# ATmegaExtOscillator.net
KiCad netlist of a schematic drawn in EAGLE
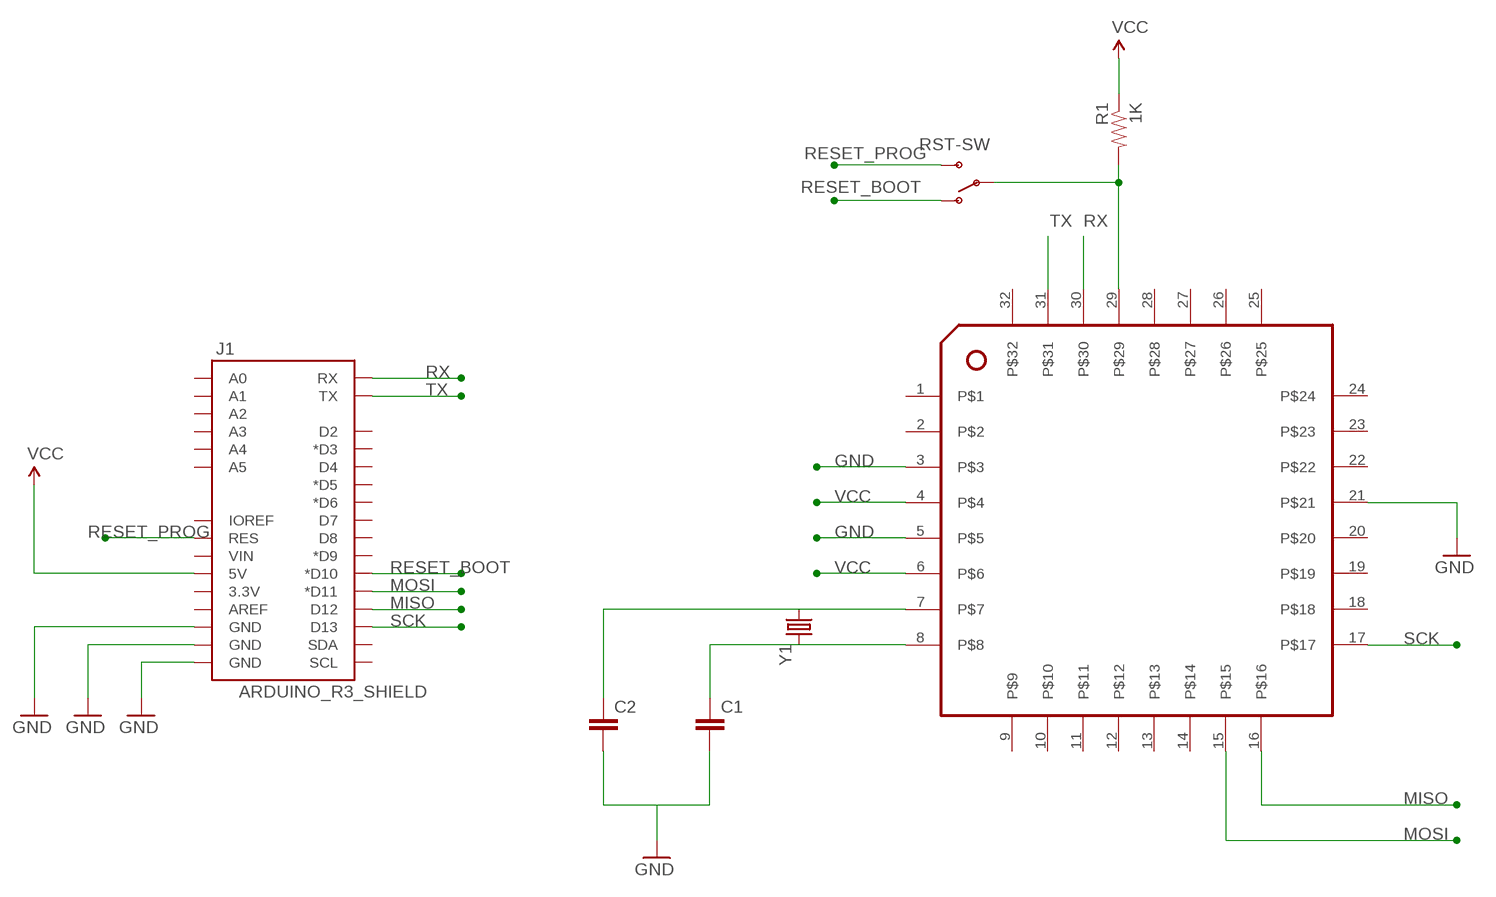
[diagram p0: schematic, sheet 1]

(export (version "E")
  (design (tool "Eeschema 10.0.6"))
  (components
    (comp (ref "C1")
      (value "0.1UF-50V-20%(PTH)KIT-EZ")
      (footprint "eagle-import:CAP-PTH-SMALL-KIT")
      (libsource (lib "eagle-import") (part "0.1UF-50V-20%(PTH)KIT-EZ"))
    )
    (comp (ref "C2")
      (value "0.1UF-50V-20%(PTH)KIT-EZ")
      (footprint "eagle-import:CAP-PTH-SMALL-KIT")
      (libsource (lib "eagle-import") (part "0.1UF-50V-20%(PTH)KIT-EZ"))
    )
    (comp (ref "J1")
      (value "ARDUINO_R3_SHIELD")
      (footprint "eagle-import:UNO_R3_SHIELD")
      (libsource (lib "eagle-import") (part "ARDUINO_R3_SHIELD"))
    )
    (comp (ref "R1")
      (value "1K")
      (footprint "eagle-import:AXIAL-0.3")
      (libsource (lib "eagle-import") (part "1KOHM-1/4W-1%(PTH)"))
    )
    (comp (ref "RST-SW")
      (value "SWITCH-SPDTPTH")
      (footprint "eagle-import:SWITCH-SPDT")
      (libsource (lib "eagle-import") (part "SWITCH-SPDTPTH"))
    )
    (comp (ref "U$1")
      (value "ATMEGA-TQFP-BREAKOUT")
      (footprint "eagle-import:TQFP32-BREAKOUT")
      (libsource (lib "eagle-import") (part "ATMEGA-TQFP-BREAKOUT"))
    )
    (comp (ref "Y1")
      (value "CRYSTALHC49US")
      (footprint "eagle-import:HC49US")
      (libsource (lib "eagle-import") (part "CRYSTALHC49US"))
    )
  )
  (nets
    (net (code "1") (name "/MISO") (class "Default")
      (node (ref "J1") (pin "D12") (pinfunction "D12_D12") (pintype "bidirectional"))
      (node (ref "U$1") (pin "16") (pinfunction "P$16_16") (pintype "bidirectional"))
    )
    (net (code "2") (name "/MOSI") (class "Default")
      (node (ref "J1") (pin "D11") (pinfunction "*D11_D11") (pintype "bidirectional"))
      (node (ref "U$1") (pin "15") (pinfunction "P$15_15") (pintype "bidirectional"))
    )
    (net (code "3") (name "/RESET_BOOT") (class "Default")
      (node (ref "J1") (pin "D10") (pinfunction "*D10_D10") (pintype "bidirectional"))
      (node (ref "RST-SW") (pin "1") (pinfunction "O_1") (pintype "passive"))
    )
    (net (code "4") (name "/RESET_PROG") (class "Default")
      (node (ref "J1") (pin "RES") (pinfunction "RES_RES") (pintype "bidirectional"))
      (node (ref "RST-SW") (pin "3") (pinfunction "S_3") (pintype "passive"))
    )
    (net (code "5") (name "/RX") (class "Default")
      (node (ref "J1") (pin "RX") (pinfunction "RX_RX") (pintype "bidirectional"))
      (node (ref "U$1") (pin "30") (pinfunction "P$30_30") (pintype "bidirectional"))
    )
    (net (code "6") (name "/SCK") (class "Default")
      (node (ref "J1") (pin "D13") (pinfunction "D13_D13") (pintype "bidirectional"))
      (node (ref "U$1") (pin "17") (pinfunction "P$17_17") (pintype "bidirectional"))
    )
    (net (code "7") (name "/TX") (class "Default")
      (node (ref "J1") (pin "TX") (pinfunction "TX_TX") (pintype "bidirectional"))
      (node (ref "U$1") (pin "31") (pinfunction "P$31_31") (pintype "bidirectional"))
    )
    (net (code "8") (name "GND") (class "Default")
      (node (ref "C1") (pin "2") (pinfunction "2_2") (pintype "passive"))
      (node (ref "C2") (pin "2") (pinfunction "2_2") (pintype "passive"))
      (node (ref "J1") (pin "GND@0") (pinfunction "GND_GND@0") (pintype "bidirectional"))
      (node (ref "J1") (pin "GND@1") (pinfunction "GND_GND@1") (pintype "bidirectional"))
      (node (ref "J1") (pin "GND@2") (pinfunction "GND_GND@2") (pintype "bidirectional"))
      (node (ref "U$1") (pin "21") (pinfunction "P$21_21") (pintype "bidirectional"))
      (node (ref "U$1") (pin "3") (pinfunction "P$3_3") (pintype "bidirectional"))
      (node (ref "U$1") (pin "5") (pinfunction "P$5_5") (pintype "bidirectional"))
    )
    (net (code "9") (name "Net-(R1-2)") (class "Default")
      (node (ref "R1") (pin "P$2") (pinfunction "2_P$2") (pintype "passive"))
      (node (ref "RST-SW") (pin "2") (pinfunction "P_2") (pintype "passive"))
      (node (ref "U$1") (pin "29") (pinfunction "P$29_29") (pintype "bidirectional"))
    )
    (net (code "10") (name "Net-(U$1-P$7)") (class "Default")
      (node (ref "C2") (pin "1") (pinfunction "1_1") (pintype "passive"))
      (node (ref "U$1") (pin "7") (pinfunction "P$7_7") (pintype "bidirectional"))
      (node (ref "Y1") (pin "1") (pinfunction "1_1") (pintype "passive"))
    )
    (net (code "11") (name "Net-(U$1-P$8)") (class "Default")
      (node (ref "C1") (pin "1") (pinfunction "1_1") (pintype "passive"))
      (node (ref "U$1") (pin "8") (pinfunction "P$8_8") (pintype "bidirectional"))
      (node (ref "Y1") (pin "2") (pinfunction "2_2") (pintype "passive"))
    )
    (net (code "12") (name "VCC") (class "Default")
      (node (ref "J1") (pin "5V") (pinfunction "5V_5V") (pintype "bidirectional"))
      (node (ref "R1") (pin "P$1") (pinfunction "1_P$1") (pintype "passive"))
      (node (ref "U$1") (pin "4") (pinfunction "P$4_4") (pintype "bidirectional"))
      (node (ref "U$1") (pin "6") (pinfunction "P$6_6") (pintype "bidirectional"))
    )
    (net (code "13") (name "unconnected-(J1-*D3-PadD3)") (class "Default")
      (node (ref "J1") (pin "D3") (pinfunction "*D3_D3") (pintype "bidirectional"))
    )
    (net (code "14") (name "unconnected-(J1-*D5-PadD5)") (class "Default")
      (node (ref "J1") (pin "D5") (pinfunction "*D5_D5") (pintype "bidirectional"))
    )
    (net (code "15") (name "unconnected-(J1-*D6-PadD6)") (class "Default")
      (node (ref "J1") (pin "D6") (pinfunction "*D6_D6") (pintype "bidirectional"))
    )
    (net (code "16") (name "unconnected-(J1-*D9-PadD9)") (class "Default")
      (node (ref "J1") (pin "D9") (pinfunction "*D9_D9") (pintype "bidirectional"))
    )
    (net (code "17") (name "unconnected-(J1-Pad3.3V)") (class "Default")
      (node (ref "J1") (pin "3.3V") (pinfunction "3.3V_3.3V") (pintype "bidirectional"))
    )
    (net (code "18") (name "unconnected-(J1-PadA0)") (class "Default")
      (node (ref "J1") (pin "A0") (pinfunction "A0_A0") (pintype "bidirectional"))
    )
    (net (code "19") (name "unconnected-(J1-PadA1)") (class "Default")
      (node (ref "J1") (pin "A1") (pinfunction "A1_A1") (pintype "bidirectional"))
    )
    (net (code "20") (name "unconnected-(J1-PadA2)") (class "Default")
      (node (ref "J1") (pin "A2") (pinfunction "A2_A2") (pintype "bidirectional"))
    )
    (net (code "21") (name "unconnected-(J1-PadA3)") (class "Default")
      (node (ref "J1") (pin "A3") (pinfunction "A3_A3") (pintype "bidirectional"))
    )
    (net (code "22") (name "unconnected-(J1-PadA4)") (class "Default")
      (node (ref "J1") (pin "A4") (pinfunction "A4_A4") (pintype "bidirectional"))
    )
    (net (code "23") (name "unconnected-(J1-PadA5)") (class "Default")
      (node (ref "J1") (pin "A5") (pinfunction "A5_A5") (pintype "bidirectional"))
    )
    (net (code "24") (name "unconnected-(J1-PadAREF)") (class "Default")
      (node (ref "J1") (pin "AREF") (pinfunction "AREF_AREF") (pintype "bidirectional"))
    )
    (net (code "25") (name "unconnected-(J1-PadD2)") (class "Default")
      (node (ref "J1") (pin "D2") (pinfunction "D2_D2") (pintype "bidirectional"))
    )
    (net (code "26") (name "unconnected-(J1-PadD4)") (class "Default")
      (node (ref "J1") (pin "D4") (pinfunction "D4_D4") (pintype "bidirectional"))
    )
    (net (code "27") (name "unconnected-(J1-PadD7)") (class "Default")
      (node (ref "J1") (pin "D7") (pinfunction "D7_D7") (pintype "bidirectional"))
    )
    (net (code "28") (name "unconnected-(J1-PadD8)") (class "Default")
      (node (ref "J1") (pin "D8") (pinfunction "D8_D8") (pintype "bidirectional"))
    )
    (net (code "29") (name "unconnected-(J1-PadIOREF)") (class "Default")
      (node (ref "J1") (pin "IOREF") (pinfunction "IOREF_IOREF") (pintype "bidirectional"))
    )
    (net (code "30") (name "unconnected-(J1-PadSCL)") (class "Default")
      (node (ref "J1") (pin "SCL") (pinfunction "SCL_SCL") (pintype "bidirectional"))
    )
    (net (code "31") (name "unconnected-(J1-PadSDA)") (class "Default")
      (node (ref "J1") (pin "SDA") (pinfunction "SDA_SDA") (pintype "bidirectional"))
    )
    (net (code "32") (name "unconnected-(J1-PadVIN)") (class "Default")
      (node (ref "J1") (pin "VIN") (pinfunction "VIN_VIN") (pintype "bidirectional"))
    )
    (net (code "33") (name "unconnected-(U$1-P$1-Pad1)") (class "Default")
      (node (ref "U$1") (pin "1") (pinfunction "P$1_1") (pintype "bidirectional"))
    )
    (net (code "34") (name "unconnected-(U$1-P$2-Pad2)") (class "Default")
      (node (ref "U$1") (pin "2") (pinfunction "P$2_2") (pintype "bidirectional"))
    )
    (net (code "35") (name "unconnected-(U$1-P$9-Pad9)") (class "Default")
      (node (ref "U$1") (pin "9") (pinfunction "P$9_9") (pintype "bidirectional"))
    )
    (net (code "36") (name "unconnected-(U$1-P$10-Pad10)") (class "Default")
      (node (ref "U$1") (pin "10") (pinfunction "P$10_10") (pintype "bidirectional"))
    )
    (net (code "37") (name "unconnected-(U$1-P$11-Pad11)") (class "Default")
      (node (ref "U$1") (pin "11") (pinfunction "P$11_11") (pintype "bidirectional"))
    )
    (net (code "38") (name "unconnected-(U$1-P$12-Pad12)") (class "Default")
      (node (ref "U$1") (pin "12") (pinfunction "P$12_12") (pintype "bidirectional"))
    )
    (net (code "39") (name "unconnected-(U$1-P$13-Pad13)") (class "Default")
      (node (ref "U$1") (pin "13") (pinfunction "P$13_13") (pintype "bidirectional"))
    )
    (net (code "40") (name "unconnected-(U$1-P$14-Pad14)") (class "Default")
      (node (ref "U$1") (pin "14") (pinfunction "P$14_14") (pintype "bidirectional"))
    )
    (net (code "41") (name "unconnected-(U$1-P$18-Pad18)") (class "Default")
      (node (ref "U$1") (pin "18") (pinfunction "P$18_18") (pintype "bidirectional"))
    )
    (net (code "42") (name "unconnected-(U$1-P$19-Pad19)") (class "Default")
      (node (ref "U$1") (pin "19") (pinfunction "P$19_19") (pintype "bidirectional"))
    )
    (net (code "43") (name "unconnected-(U$1-P$20-Pad20)") (class "Default")
      (node (ref "U$1") (pin "20") (pinfunction "P$20_20") (pintype "bidirectional"))
    )
    (net (code "44") (name "unconnected-(U$1-P$22-Pad22)") (class "Default")
      (node (ref "U$1") (pin "22") (pinfunction "P$22_22") (pintype "bidirectional"))
    )
    (net (code "45") (name "unconnected-(U$1-P$23-Pad23)") (class "Default")
      (node (ref "U$1") (pin "23") (pinfunction "P$23_23") (pintype "bidirectional"))
    )
    (net (code "46") (name "unconnected-(U$1-P$24-Pad24)") (class "Default")
      (node (ref "U$1") (pin "24") (pinfunction "P$24_24") (pintype "bidirectional"))
    )
    (net (code "47") (name "unconnected-(U$1-P$25-Pad25)") (class "Default")
      (node (ref "U$1") (pin "25") (pinfunction "P$25_25") (pintype "bidirectional"))
    )
    (net (code "48") (name "unconnected-(U$1-P$26-Pad26)") (class "Default")
      (node (ref "U$1") (pin "26") (pinfunction "P$26_26") (pintype "bidirectional"))
    )
    (net (code "49") (name "unconnected-(U$1-P$27-Pad27)") (class "Default")
      (node (ref "U$1") (pin "27") (pinfunction "P$27_27") (pintype "bidirectional"))
    )
    (net (code "50") (name "unconnected-(U$1-P$28-Pad28)") (class "Default")
      (node (ref "U$1") (pin "28") (pinfunction "P$28_28") (pintype "bidirectional"))
    )
    (net (code "51") (name "unconnected-(U$1-P$32-Pad32)") (class "Default")
      (node (ref "U$1") (pin "32") (pinfunction "P$32_32") (pintype "bidirectional"))
    )
  )
)
